# awm661tx.net
KiCad netlist of a schematic drawn in EAGLE
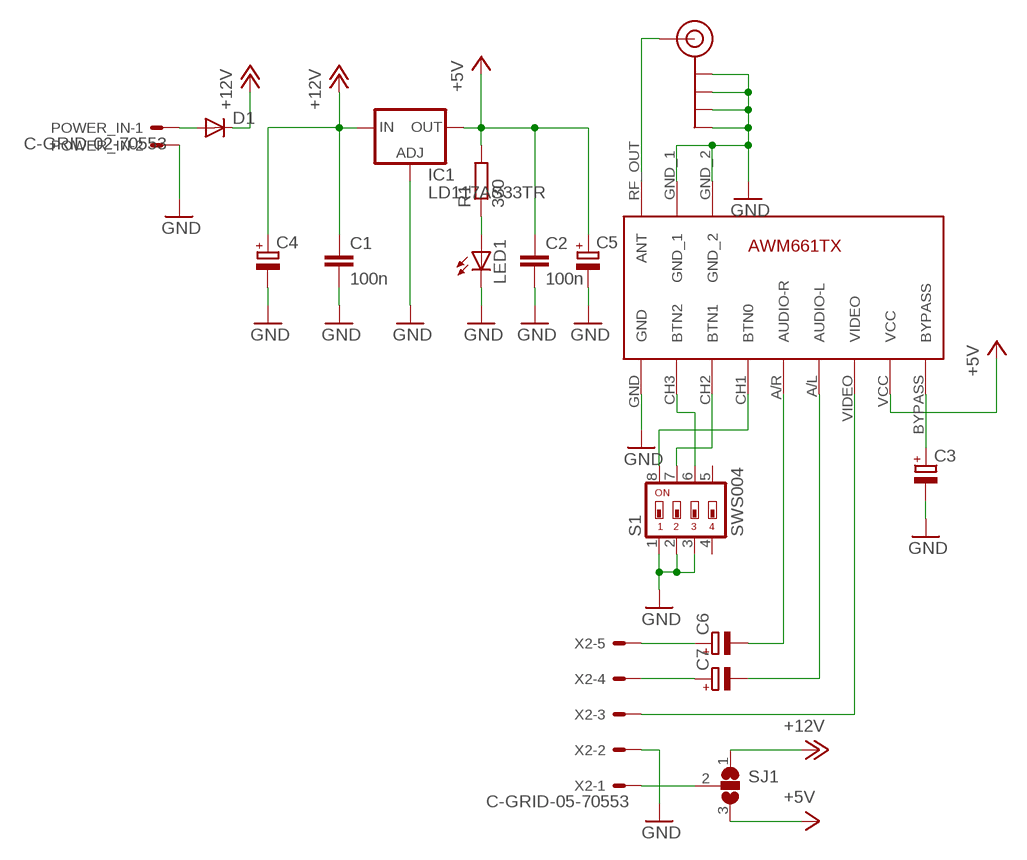
[diagram p0: schematic, sheet 1]

(export (version "E")
  (design (tool "Eeschema 10.0.6"))
  (components
    (comp (ref "C1")
      (value "100n")
      (footprint "eagle-import:C0805")
      (libsource (lib "eagle-import") (part "C-EUC0805"))
    )
    (comp (ref "C2")
      (value "100n")
      (footprint "eagle-import:C0805")
      (libsource (lib "eagle-import") (part "C-EUC0805"))
    )
    (comp (ref "C3")
      (value "CPOL-EU150CLZ-0810")
      (footprint "eagle-import:150CLZ-0810")
      (libsource (lib "eagle-import") (part "CPOL-EU150CLZ-0810"))
    )
    (comp (ref "C4")
      (value "CPOL-EU150CLZ-0810")
      (footprint "eagle-import:150CLZ-0810")
      (libsource (lib "eagle-import") (part "CPOL-EU150CLZ-0810"))
    )
    (comp (ref "C5")
      (value "CPOL-EU150CLZ-0810")
      (footprint "eagle-import:150CLZ-0810")
      (libsource (lib "eagle-import") (part "CPOL-EU150CLZ-0810"))
    )
    (comp (ref "C6")
      (value "CPOL-EU153CLV-0505")
      (footprint "eagle-import:153CLV-0505")
      (libsource (lib "eagle-import") (part "CPOL-EU153CLV-0505"))
    )
    (comp (ref "C7")
      (value "CPOL-EU153CLV-0505")
      (footprint "eagle-import:153CLV-0505")
      (libsource (lib "eagle-import") (part "CPOL-EU153CLV-0505"))
    )
    (comp (ref "D1")
      (value "DIODE-MELF-MLL41")
      (footprint "eagle-import:MELF-MLL41")
      (libsource (lib "eagle-import") (part "DIODE-MELF-MLL41"))
    )
    (comp (ref "IC1")
      (value "LD117AS33TR")
      (footprint "eagle-import:SOT223")
      (libsource (lib "eagle-import") (part "LD117A?S33TR"))
    )
    (comp (ref "J$1")
      (value "SMA_EDGE")
      (footprint "eagle-import:SMA-EDGE")
      (libsource (lib "eagle-import") (part "SMA_EDGE"))
    )
    (comp (ref "LED1")
      (value "LEDCHIP-LED0805")
      (footprint "eagle-import:CHIP-LED0805")
      (libsource (lib "eagle-import") (part "LEDCHIP-LED0805"))
    )
    (comp (ref "POWER_IN")
      (value "C-GRID-02-70553")
      (footprint "eagle-import:70553-02")
      (libsource (lib "eagle-import") (part "C-GRID-02-70553"))
    )
    (comp (ref "R1")
      (value "330")
      (footprint "eagle-import:R0805")
      (libsource (lib "eagle-import") (part "R-EU_R0805"))
    )
    (comp (ref "S1")
      (value "SWS004")
      (footprint "eagle-import:SMS-004")
      (libsource (lib "eagle-import") (part "SWS004"))
    )
    (comp (ref "SJ1")
      (value "SJ2W")
      (footprint "eagle-import:SJ_2")
      (libsource (lib "eagle-import") (part "SJ2W"))
    )
    (comp (ref "U$1")
      (value "AWM661TX")
      (footprint "eagle-import:AWM661TX")
      (libsource (lib "eagle-import") (part "AWM661TX"))
    )
    (comp (ref "X2")
      (value "C-GRID-05-70553")
      (footprint "eagle-import:70553-05")
      (libsource (lib "eagle-import") (part "C-GRID-05-70553"))
    )
  )
  (nets
    (net (code "1") (name "+5V") (class "Default")
      (node (ref "C2") (pin "1") (pinfunction "1_1") (pintype "passive"))
      (node (ref "C5") (pin "+") (pinfunction "+_+") (pintype "passive"))
      (node (ref "IC1") (pin "4") (pinfunction "OUT_4") (pintype "passive"))
      (node (ref "R1") (pin "2") (pinfunction "2_2") (pintype "passive"))
      (node (ref "SJ1") (pin "3") (pinfunction "3_3") (pintype "passive"))
      (node (ref "U$1") (pin "VCC") (pinfunction "VCC_VCC") (pintype "bidirectional"))
    )
    (net (code "2") (name "+12V") (class "Default")
      (node (ref "C1") (pin "1") (pinfunction "1_1") (pintype "passive"))
      (node (ref "C4") (pin "+") (pinfunction "+_+") (pintype "passive"))
      (node (ref "D1") (pin "C") (pinfunction "C_C") (pintype "passive"))
      (node (ref "IC1") (pin "3") (pinfunction "IN_3") (pintype "input"))
      (node (ref "SJ1") (pin "1") (pinfunction "1_1") (pintype "passive"))
    )
    (net (code "3") (name "GND") (class "Default")
      (node (ref "C1") (pin "2") (pinfunction "2_2") (pintype "passive"))
      (node (ref "C2") (pin "2") (pinfunction "2_2") (pintype "passive"))
      (node (ref "C3") (pin "-") (pinfunction "-_-") (pintype "passive"))
      (node (ref "C4") (pin "-") (pinfunction "-_-") (pintype "passive"))
      (node (ref "C5") (pin "-") (pinfunction "-_-") (pintype "passive"))
      (node (ref "IC1") (pin "1") (pinfunction "ADJ_1") (pintype "input"))
      (node (ref "J$1") (pin "GND@0") (pinfunction "GND_GND@0") (pintype "bidirectional"))
      (node (ref "J$1") (pin "GND@1") (pinfunction "GND_GND@1") (pintype "bidirectional"))
      (node (ref "J$1") (pin "GND@2") (pinfunction "GND_GND@2") (pintype "bidirectional"))
      (node (ref "J$1") (pin "GND@3") (pinfunction "GND_GND@3") (pintype "bidirectional"))
      (node (ref "LED1") (pin "C") (pinfunction "C_C") (pintype "passive"))
      (node (ref "POWER_IN") (pin "2") (pinfunction "S_2") (pintype "passive"))
      (node (ref "S1") (pin "1") (pinfunction "1_1") (pintype "passive"))
      (node (ref "S1") (pin "2") (pinfunction "2_2") (pintype "passive"))
      (node (ref "S1") (pin "3") (pinfunction "3_3") (pintype "passive"))
      (node (ref "U$1") (pin "GND") (pinfunction "GND_GND") (pintype "bidirectional"))
      (node (ref "U$1") (pin "GND_1") (pinfunction "GND_1_GND_1") (pintype "bidirectional"))
      (node (ref "U$1") (pin "GND_2") (pinfunction "GND_2_GND_2") (pintype "bidirectional"))
      (node (ref "X2") (pin "2") (pinfunction "S_2") (pintype "passive"))
    )
    (net (code "4") (name "Net-(C3-Pad+)") (class "Default")
      (node (ref "C3") (pin "+") (pinfunction "+_+") (pintype "passive"))
      (node (ref "U$1") (pin "BYPASS") (pinfunction "BYPASS_BYPASS") (pintype "bidirectional"))
    )
    (net (code "5") (name "Net-(J$1-SIGNAL)") (class "Default")
      (node (ref "J$1") (pin "SIG") (pinfunction "SIGNAL_SIG") (pintype "bidirectional"))
      (node (ref "U$1") (pin "RF_OUT") (pinfunction "ANT_RF_OUT") (pintype "bidirectional"))
    )
    (net (code "6") (name "Net-(LED1-PadA)") (class "Default")
      (node (ref "LED1") (pin "A") (pinfunction "A_A") (pintype "passive"))
      (node (ref "R1") (pin "1") (pinfunction "1_1") (pintype "passive"))
    )
    (net (code "7") (name "Net-(POWER_INA-S)") (class "Default")
      (node (ref "D1") (pin "A") (pinfunction "A_A") (pintype "passive"))
      (node (ref "POWER_IN") (pin "1") (pinfunction "S_1") (pintype "passive"))
    )
    (net (code "8") (name "Net-(U$1-AUDIO-L)") (class "Default")
      (node (ref "C7") (pin "-") (pinfunction "-_-") (pintype "passive"))
      (node (ref "U$1") (pin "A/L") (pinfunction "AUDIO-L_A/L") (pintype "bidirectional"))
    )
    (net (code "9") (name "Net-(U$1-AUDIO-R)") (class "Default")
      (node (ref "C6") (pin "-") (pinfunction "-_-") (pintype "passive"))
      (node (ref "U$1") (pin "A/R") (pinfunction "AUDIO-R_A/R") (pintype "bidirectional"))
    )
    (net (code "10") (name "Net-(U$1-BTN0)") (class "Default")
      (node (ref "S1") (pin "8") (pinfunction "8_8") (pintype "passive"))
      (node (ref "U$1") (pin "CH1") (pinfunction "BTN0_CH1") (pintype "bidirectional"))
    )
    (net (code "11") (name "Net-(U$1-BTN1)") (class "Default")
      (node (ref "S1") (pin "7") (pinfunction "7_7") (pintype "passive"))
      (node (ref "U$1") (pin "CH2") (pinfunction "BTN1_CH2") (pintype "bidirectional"))
    )
    (net (code "12") (name "Net-(U$1-BTN2)") (class "Default")
      (node (ref "S1") (pin "6") (pinfunction "6_6") (pintype "passive"))
      (node (ref "U$1") (pin "CH3") (pinfunction "BTN2_CH3") (pintype "bidirectional"))
    )
    (net (code "13") (name "Net-(X2A-S)") (class "Default")
      (node (ref "SJ1") (pin "2") (pinfunction "2_2") (pintype "passive"))
      (node (ref "X2") (pin "1") (pinfunction "S_1") (pintype "passive"))
    )
    (net (code "14") (name "Net-(X2C-S)") (class "Default")
      (node (ref "U$1") (pin "VIDEO") (pinfunction "VIDEO_VIDEO") (pintype "bidirectional"))
      (node (ref "X2") (pin "3") (pinfunction "S_3") (pintype "passive"))
    )
    (net (code "15") (name "Net-(X2D-S)") (class "Default")
      (node (ref "C7") (pin "+") (pinfunction "+_+") (pintype "passive"))
      (node (ref "X2") (pin "4") (pinfunction "S_4") (pintype "passive"))
    )
    (net (code "16") (name "Net-(X2E-S)") (class "Default")
      (node (ref "C6") (pin "+") (pinfunction "+_+") (pintype "passive"))
      (node (ref "X2") (pin "5") (pinfunction "S_5") (pintype "passive"))
    )
    (net (code "17") (name "unconnected-(S1-Pad4)") (class "Default")
      (node (ref "S1") (pin "4") (pinfunction "4_4") (pintype "passive"))
    )
    (net (code "18") (name "unconnected-(S1-Pad5)") (class "Default")
      (node (ref "S1") (pin "5") (pinfunction "5_5") (pintype "passive"))
    )
  )
)
